# NFC_Shield.net
KiCad netlist of a schematic drawn in EAGLE
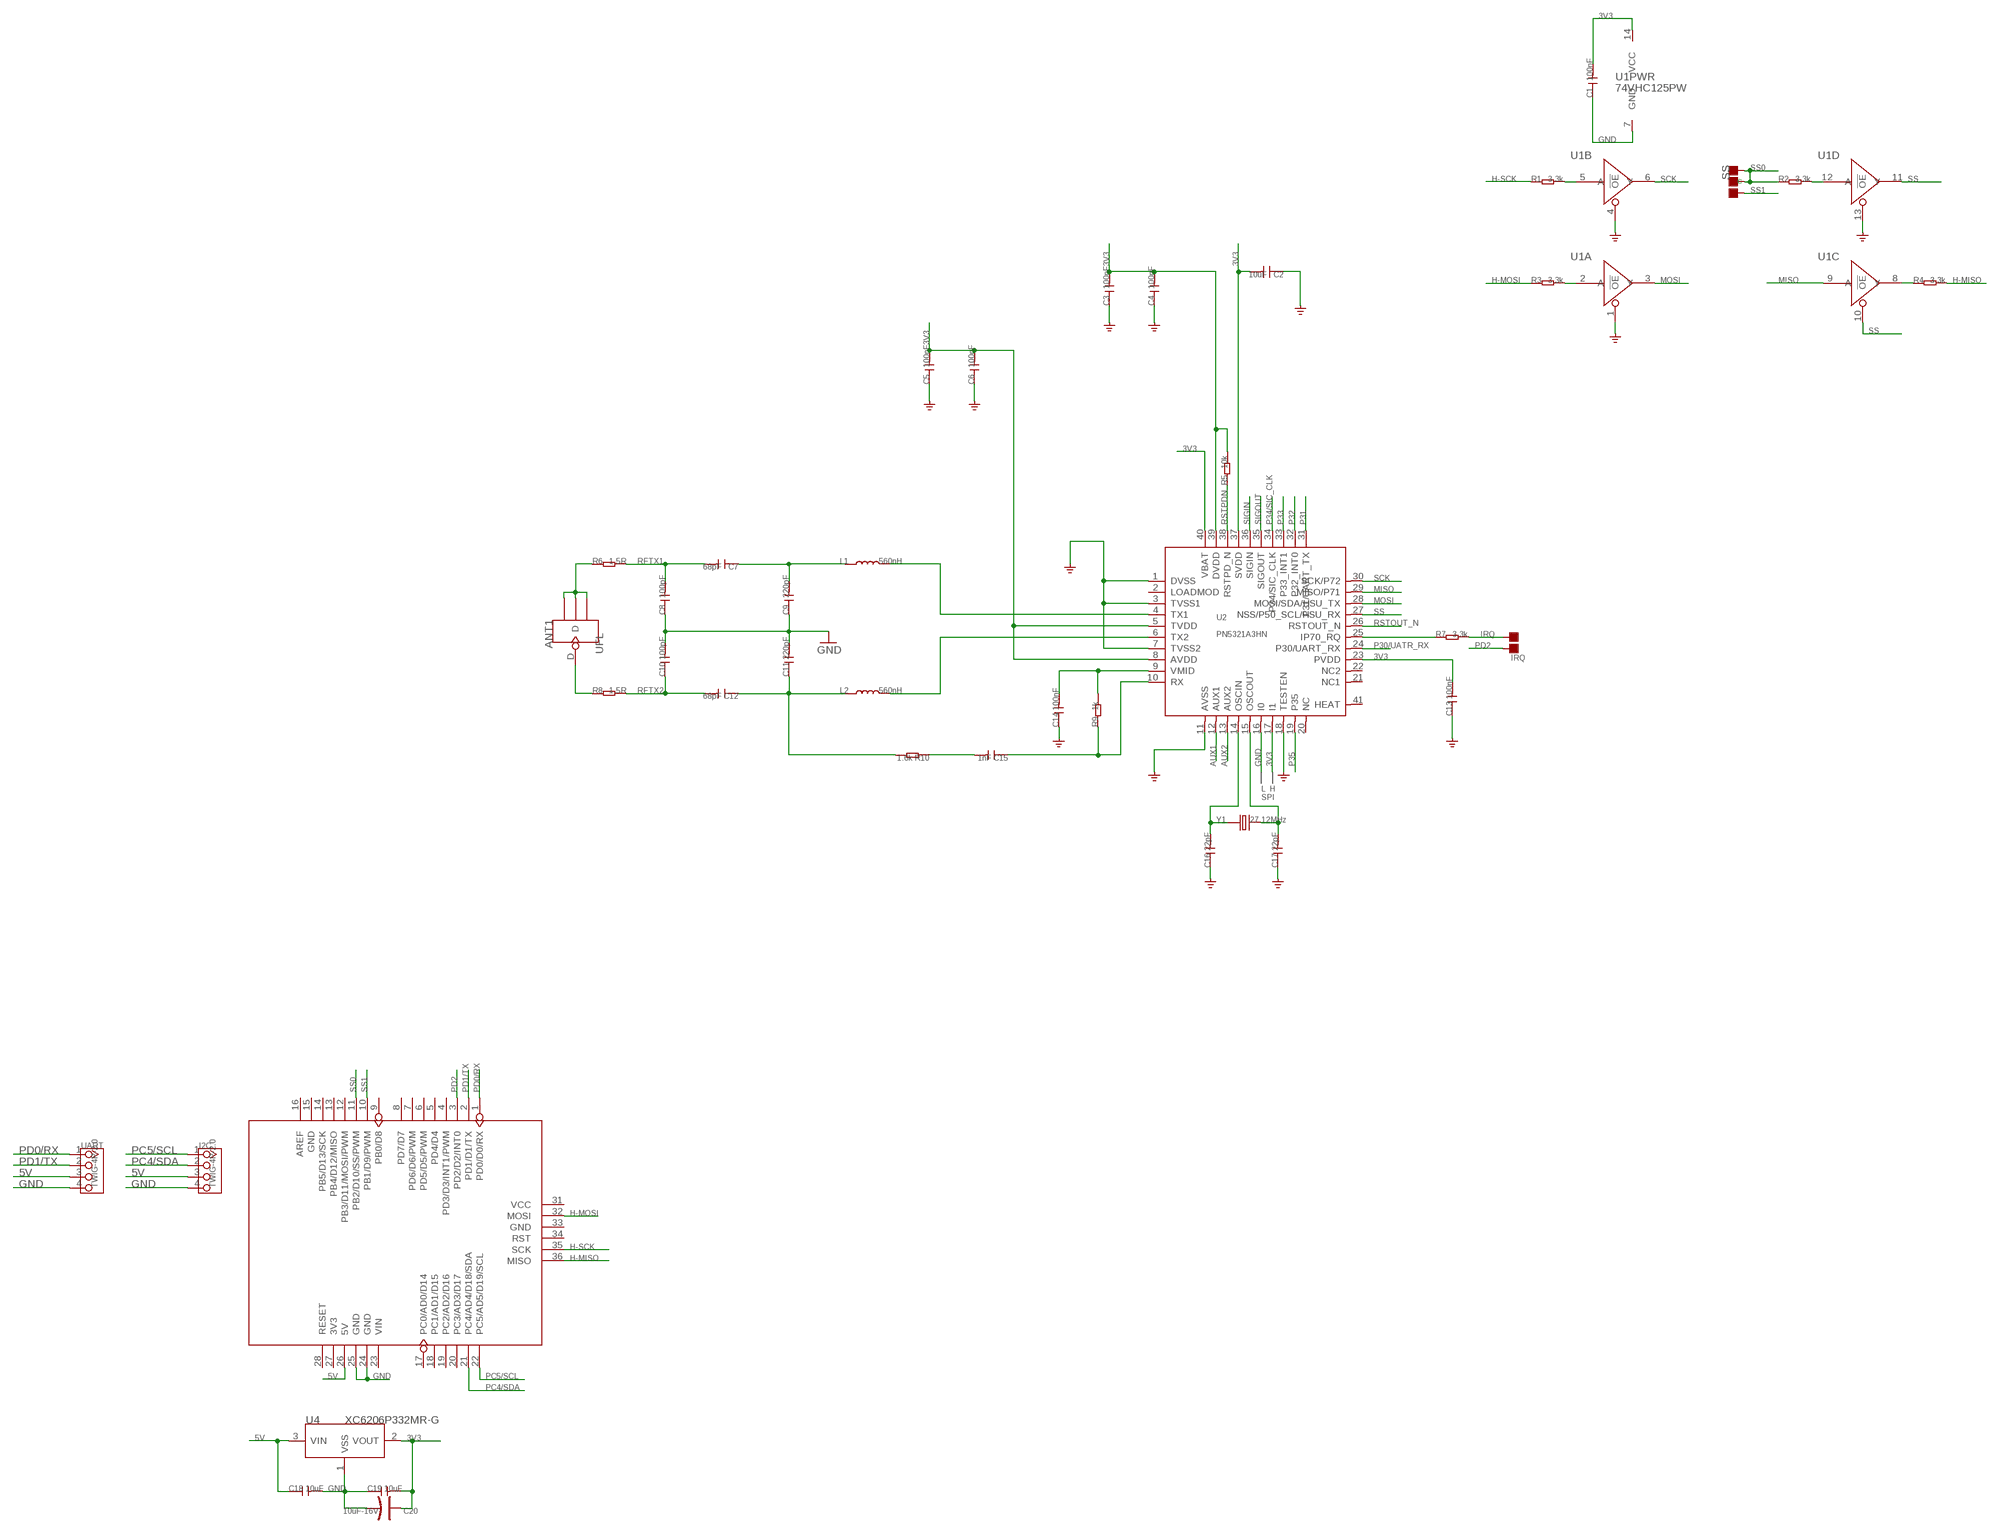
[diagram p0: schematic, sheet 1]

(export (version "E")
  (design (tool "Eeschema 10.0.6"))
  (components
    (comp (ref "ANT1")
      (value "UFL")
      (footprint "eagle-import:4P-U-FL")
      (libsource (lib "eagle-import") (part "ANTENNA-U-FL"))
    )
    (comp (ref "C1")
      (value "100nF")
      (footprint "eagle-import:C0603")
      (libsource (lib "eagle-import") (part "C-0603"))
    )
    (comp (ref "C2")
      (value "10uF")
      (footprint "eagle-import:0805")
      (libsource (lib "eagle-import") (part "Discreter_C-0805"))
    )
    (comp (ref "C3")
      (value "100nF")
      (footprint "eagle-import:C0603")
      (libsource (lib "eagle-import") (part "C-0603"))
    )
    (comp (ref "C4")
      (value "100nF")
      (footprint "eagle-import:C0603")
      (libsource (lib "eagle-import") (part "C-0603"))
    )
    (comp (ref "C5")
      (value "100nF")
      (footprint "eagle-import:C0603")
      (libsource (lib "eagle-import") (part "C-0603"))
    )
    (comp (ref "C6")
      (value "100nF")
      (footprint "eagle-import:C0603")
      (libsource (lib "eagle-import") (part "C-0603"))
    )
    (comp (ref "C7")
      (value "68pF")
      (footprint "eagle-import:C0603")
      (libsource (lib "eagle-import") (part "C-0603"))
    )
    (comp (ref "C8")
      (value "100pF")
      (footprint "eagle-import:C0603")
      (libsource (lib "eagle-import") (part "C-0603"))
    )
    (comp (ref "C9")
      (value "220pF")
      (footprint "eagle-import:C0603")
      (libsource (lib "eagle-import") (part "C-0603"))
    )
    (comp (ref "C10")
      (value "100pF")
      (footprint "eagle-import:C0603")
      (libsource (lib "eagle-import") (part "C-0603"))
    )
    (comp (ref "C11")
      (value "220pF")
      (footprint "eagle-import:C0603")
      (libsource (lib "eagle-import") (part "C-0603"))
    )
    (comp (ref "C12")
      (value "68pF")
      (footprint "eagle-import:C0603")
      (libsource (lib "eagle-import") (part "C-0603"))
    )
    (comp (ref "C13")
      (value "100nF")
      (footprint "eagle-import:C0603")
      (libsource (lib "eagle-import") (part "C-0603"))
    )
    (comp (ref "C14")
      (value "100nF")
      (footprint "eagle-import:C0603")
      (libsource (lib "eagle-import") (part "C-0603"))
    )
    (comp (ref "C15")
      (value "1nF")
      (footprint "eagle-import:C0603")
      (libsource (lib "eagle-import") (part "C-0603"))
    )
    (comp (ref "C16")
      (value "22pF")
      (footprint "eagle-import:C0603")
      (libsource (lib "eagle-import") (part "C-0603"))
    )
    (comp (ref "C17")
      (value "22pF")
      (footprint "eagle-import:C0603")
      (libsource (lib "eagle-import") (part "C-0603"))
    )
    (comp (ref "C18")
      (value "10uF")
      (footprint "eagle-import:C0805")
      (libsource (lib "eagle-import") (part "C-0805"))
    )
    (comp (ref "C19")
      (value "10uF")
      (footprint "eagle-import:C0805")
      (libsource (lib "eagle-import") (part "C-0805"))
    )
    (comp (ref "C20")
      (value "10uF-16V")
      (footprint "eagle-import:AVX-A")
      (libsource (lib "eagle-import") (part "CAP-AVX-A"))
    )
    (comp (ref "I2C")
      (value "TWIG-4P-2.0")
      (footprint "eagle-import:4P-2.0")
      (libsource (lib "eagle-import") (part "TWIG-4P-2.0-2.0"))
    )
    (comp (ref "IRQ")
      (value "DNP")
      (footprint "eagle-import:2P-SMD-1.78X1.27")
      (libsource (lib "eagle-import") (part "PAD-JUMPER-2P"))
    )
    (comp (ref "L1")
      (value "560nH")
      (footprint "eagle-import:L0805")
      (libsource (lib "eagle-import") (part "L'0805'"))
    )
    (comp (ref "L2")
      (value "560nH")
      (footprint "eagle-import:L0805")
      (libsource (lib "eagle-import") (part "L'0805'"))
    )
    (comp (ref "R1")
      (value "3.3k")
      (footprint "eagle-import:R0603")
      (libsource (lib "eagle-import") (part "R-0603"))
    )
    (comp (ref "R2")
      (value "3.3k")
      (footprint "eagle-import:R0603")
      (libsource (lib "eagle-import") (part "R-0603"))
    )
    (comp (ref "R3")
      (value "3.3k")
      (footprint "eagle-import:R0603")
      (libsource (lib "eagle-import") (part "R-0603"))
    )
    (comp (ref "R4")
      (value "3.3k")
      (footprint "eagle-import:R0603")
      (libsource (lib "eagle-import") (part "R-0603"))
    )
    (comp (ref "R5")
      (value "10k")
      (footprint "eagle-import:R0603")
      (libsource (lib "eagle-import") (part "R-0603"))
    )
    (comp (ref "R6")
      (value "1.5R")
      (footprint "eagle-import:R0603")
      (libsource (lib "eagle-import") (part "R-0603"))
    )
    (comp (ref "R7")
      (value "3.3k")
      (footprint "eagle-import:R0603")
      (libsource (lib "eagle-import") (part "R-0603"))
    )
    (comp (ref "R8")
      (value "1.5R")
      (footprint "eagle-import:R0603")
      (libsource (lib "eagle-import") (part "R-0603"))
    )
    (comp (ref "R9")
      (value "1k")
      (footprint "eagle-import:R0603")
      (libsource (lib "eagle-import") (part "R-0603"))
    )
    (comp (ref "R10")
      (value "1.6k")
      (footprint "eagle-import:R0603")
      (libsource (lib "eagle-import") (part "R-0603"))
    )
    (comp (ref "SS")
      (value "DNP")
      (footprint "eagle-import:3P-SMD-4.1X1.5")
      (libsource (lib "eagle-import") (part "PAD-JUMPER-3P-4040"))
    )
    (comp (ref "U1")
      (value "74VHC125PW")
      (footprint "eagle-import:TSSOP14")
      (libsource (lib "eagle-import") (part "74V125PWHC"))
    )
    (comp (ref "U2")
      (value "PN5321A3HN")
      (footprint "eagle-import:HVQFN40")
      (libsource (lib "eagle-import") (part "PN532-HVQFN40"))
    )
    (comp (ref "U3")
      (value "ARDUINO'W/-SILK")
      (footprint "eagle-import:ARDUINO")
      (libsource (lib "eagle-import") (part "ARDUINO'W/-SILK"))
    )
    (comp (ref "U4")
      (value "XC6206P332MR-G")
      (footprint "eagle-import:SOT23")
      (libsource (lib "eagle-import") (part "XC6206MR"))
    )
    (comp (ref "UART")
      (value "TWIG-4P-2.0")
      (footprint "eagle-import:4P-2.0")
      (libsource (lib "eagle-import") (part "TWIG-4P-2.0-2.0"))
    )
    (comp (ref "Y1")
      (value "27.12MHz")
      (footprint "eagle-import:HC49_S")
      (libsource (lib "eagle-import") (part "CRYSTAL'HC49S'"))
    )
  )
  (nets
    (net (code "1") (name "/3V3") (class "Default")
      (node (ref "C1") (pin "2") (pinfunction "2_2") (pintype "passive"))
      (node (ref "C13") (pin "2") (pinfunction "2_2") (pintype "passive"))
      (node (ref "C19") (pin "2") (pinfunction "2_2") (pintype "passive"))
      (node (ref "C2") (pin "2") (pinfunction "2_2") (pintype "passive"))
      (node (ref "C20") (pin "+") (pinfunction "+_+") (pintype "passive"))
      (node (ref "C3") (pin "2") (pinfunction "2_2") (pintype "passive"))
      (node (ref "C4") (pin "2") (pinfunction "2_2") (pintype "passive"))
      (node (ref "C5") (pin "2") (pinfunction "2_2") (pintype "passive"))
      (node (ref "C6") (pin "2") (pinfunction "2_2") (pintype "passive"))
      (node (ref "R5") (pin "2") (pinfunction "2_2") (pintype "passive"))
      (node (ref "U1") (pin "14") (pinfunction "VCC_14") (pintype "power_in"))
      (node (ref "U2") (pin "17") (pinfunction "I1_17") (pintype "input"))
      (node (ref "U2") (pin "23") (pinfunction "PVDD_23") (pintype "power_in"))
      (node (ref "U2") (pin "37") (pinfunction "SVDD_37") (pintype "power_in"))
      (node (ref "U2") (pin "39") (pinfunction "DVDD_39") (pintype "power_in"))
      (node (ref "U2") (pin "40") (pinfunction "VBAT_40") (pintype "power_in"))
      (node (ref "U2") (pin "5") (pinfunction "TVDD_5") (pintype "power_in"))
      (node (ref "U2") (pin "8") (pinfunction "AVDD_8") (pintype "power_in"))
      (node (ref "U4") (pin "2") (pinfunction "VOUT_2") (pintype "output"))
    )
    (net (code "2") (name "/5V") (class "Default")
      (node (ref "C18") (pin "1") (pinfunction "1_1") (pintype "passive"))
      (node (ref "I2C") (pin "3") (pinfunction "3_3") (pintype "bidirectional"))
      (node (ref "U3") (pin "26") (pinfunction "5V_26") (pintype "bidirectional"))
      (node (ref "U4") (pin "3") (pinfunction "VIN_3") (pintype "input"))
      (node (ref "UART") (pin "3") (pinfunction "3_3") (pintype "bidirectional"))
    )
    (net (code "3") (name "/AUX1") (class "Default")
      (node (ref "U2") (pin "12") (pinfunction "AUX1_12") (pintype "output"))
    )
    (net (code "4") (name "/AUX2") (class "Default")
      (node (ref "U2") (pin "13") (pinfunction "AUX2_13") (pintype "output"))
    )
    (net (code "5") (name "/H-MISO") (class "Default")
      (node (ref "R4") (pin "2") (pinfunction "2_2") (pintype "passive"))
      (node (ref "U3") (pin "36") (pinfunction "MISO_36") (pintype "bidirectional"))
    )
    (net (code "6") (name "/H-MOSI") (class "Default")
      (node (ref "R3") (pin "1") (pinfunction "1_1") (pintype "passive"))
      (node (ref "U3") (pin "32") (pinfunction "MOSI_32") (pintype "bidirectional"))
    )
    (net (code "7") (name "/H-SCK") (class "Default")
      (node (ref "R1") (pin "1") (pinfunction "1_1") (pintype "passive"))
      (node (ref "U3") (pin "35") (pinfunction "SCK_35") (pintype "bidirectional"))
    )
    (net (code "8") (name "/IRQ") (class "Default")
      (node (ref "IRQ") (pin "1") (pinfunction "1_1") (pintype "bidirectional"))
      (node (ref "R7") (pin "2") (pinfunction "2_2") (pintype "passive"))
    )
    (net (code "9") (name "/MISO") (class "Default")
      (node (ref "U1") (pin "9") (pinfunction "A_9") (pintype "bidirectional"))
      (node (ref "U2") (pin "29") (pinfunction "MISO/P71_29") (pintype "bidirectional"))
    )
    (net (code "10") (name "/MOSI") (class "Default")
      (node (ref "U1") (pin "3") (pinfunction "Y_3") (pintype "bidirectional"))
      (node (ref "U2") (pin "28") (pinfunction "MOSI/SDA/HSU_TX_28") (pintype "bidirectional"))
    )
    (net (code "11") (name "/P30{slash}UATR_RX") (class "Default")
      (node (ref "U2") (pin "24") (pinfunction "P30/UART_RX_24") (pintype "bidirectional"))
    )
    (net (code "12") (name "/P31") (class "Default")
      (node (ref "U2") (pin "31") (pinfunction "P31/UART_TX_31") (pintype "bidirectional"))
    )
    (net (code "13") (name "/P32") (class "Default")
      (node (ref "U2") (pin "32") (pinfunction "P32_INT0_32") (pintype "bidirectional"))
    )
    (net (code "14") (name "/P33") (class "Default")
      (node (ref "U2") (pin "33") (pinfunction "P33_INT1_33") (pintype "bidirectional"))
    )
    (net (code "15") (name "/P34{slash}SIC_CLK") (class "Default")
      (node (ref "U2") (pin "34") (pinfunction "P34/SIC_CLK_34") (pintype "bidirectional"))
    )
    (net (code "16") (name "/P35") (class "Default")
      (node (ref "U2") (pin "19") (pinfunction "P35_19") (pintype "bidirectional"))
    )
    (net (code "17") (name "/PC4{slash}SDA") (class "Default")
      (node (ref "I2C") (pin "2") (pinfunction "2_2") (pintype "bidirectional"))
      (node (ref "U3") (pin "21") (pinfunction "PC4/AD4/D18/SDA_21") (pintype "bidirectional"))
    )
    (net (code "18") (name "/PC5{slash}SCL") (class "Default")
      (node (ref "I2C") (pin "1") (pinfunction "1_1") (pintype "bidirectional"))
      (node (ref "U3") (pin "22") (pinfunction "PC5/AD5/D19/SCL_22") (pintype "bidirectional"))
    )
    (net (code "19") (name "/PD0{slash}RX") (class "Default")
      (node (ref "U3") (pin "1") (pinfunction "PD0/D0/RX_1") (pintype "bidirectional"))
      (node (ref "UART") (pin "1") (pinfunction "1_1") (pintype "bidirectional"))
    )
    (net (code "20") (name "/PD1{slash}TX") (class "Default")
      (node (ref "U3") (pin "2") (pinfunction "PD1/D1/TX_2") (pintype "bidirectional"))
      (node (ref "UART") (pin "2") (pinfunction "2_2") (pintype "bidirectional"))
    )
    (net (code "21") (name "/PD2") (class "Default")
      (node (ref "IRQ") (pin "2") (pinfunction "2_2") (pintype "bidirectional"))
      (node (ref "U3") (pin "3") (pinfunction "PD2/D2/INT0_3") (pintype "bidirectional"))
    )
    (net (code "22") (name "/RFTX1") (class "Default")
      (node (ref "C7") (pin "2") (pinfunction "2_2") (pintype "passive"))
      (node (ref "C8") (pin "2") (pinfunction "2_2") (pintype "passive"))
      (node (ref "R6") (pin "2") (pinfunction "2_2") (pintype "passive"))
    )
    (net (code "23") (name "/RFTX2") (class "Default")
      (node (ref "C10") (pin "1") (pinfunction "1_1") (pintype "passive"))
      (node (ref "C12") (pin "2") (pinfunction "2_2") (pintype "passive"))
      (node (ref "R8") (pin "2") (pinfunction "2_2") (pintype "passive"))
    )
    (net (code "24") (name "/RSTOUT_N") (class "Default")
      (node (ref "U2") (pin "26") (pinfunction "RSTOUT_N_26") (pintype "bidirectional"))
    )
    (net (code "25") (name "/RSTPDN") (class "Default")
      (node (ref "R5") (pin "1") (pinfunction "1_1") (pintype "passive"))
      (node (ref "U2") (pin "38") (pinfunction "RSTPD_N_38") (pintype "input"))
    )
    (net (code "26") (name "/SCK") (class "Default")
      (node (ref "U1") (pin "6") (pinfunction "Y_6") (pintype "bidirectional"))
      (node (ref "U2") (pin "30") (pinfunction "SCK/P72_30") (pintype "bidirectional"))
    )
    (net (code "27") (name "/SIGIN") (class "Default")
      (node (ref "U2") (pin "36") (pinfunction "SIGIN_36") (pintype "input"))
    )
    (net (code "28") (name "/SIGOUT") (class "Default")
      (node (ref "U2") (pin "35") (pinfunction "SIGOUT_35") (pintype "output"))
    )
    (net (code "29") (name "/SS") (class "Default")
      (node (ref "U1") (pin "10") (pinfunction "~{OE}_10") (pintype "bidirectional"))
      (node (ref "U1") (pin "11") (pinfunction "Y_11") (pintype "bidirectional"))
      (node (ref "U2") (pin "27") (pinfunction "NSS/P50_SCL/HSU_RX_27") (pintype "bidirectional"))
    )
    (net (code "30") (name "/SS0") (class "Default")
      (node (ref "R2") (pin "1") (pinfunction "1_1") (pintype "passive"))
      (node (ref "SS") (pin "11") (pinfunction "R_11") (pintype "bidirectional"))
      (node (ref "SS") (pin "MM") (pinfunction "C_MM") (pintype "bidirectional"))
      (node (ref "U3") (pin "11") (pinfunction "PB2/D10/SS/PWM_11") (pintype "bidirectional"))
    )
    (net (code "31") (name "/SS1") (class "Default")
      (node (ref "SS") (pin "00") (pinfunction "L_00") (pintype "bidirectional"))
      (node (ref "U3") (pin "10") (pinfunction "PB1/D9/PWM_10") (pintype "bidirectional"))
    )
    (net (code "32") (name "GND") (class "Default")
      (node (ref "C1") (pin "1") (pinfunction "1_1") (pintype "passive"))
      (node (ref "C10") (pin "2") (pinfunction "2_2") (pintype "passive"))
      (node (ref "C11") (pin "2") (pinfunction "2_2") (pintype "passive"))
      (node (ref "C13") (pin "1") (pinfunction "1_1") (pintype "passive"))
      (node (ref "C14") (pin "1") (pinfunction "1_1") (pintype "passive"))
      (node (ref "C16") (pin "1") (pinfunction "1_1") (pintype "passive"))
      (node (ref "C17") (pin "1") (pinfunction "1_1") (pintype "passive"))
      (node (ref "C18") (pin "2") (pinfunction "2_2") (pintype "passive"))
      (node (ref "C19") (pin "1") (pinfunction "1_1") (pintype "passive"))
      (node (ref "C2") (pin "1") (pinfunction "1_1") (pintype "passive"))
      (node (ref "C20") (pin "-") (pinfunction "-_-") (pintype "passive"))
      (node (ref "C3") (pin "1") (pinfunction "1_1") (pintype "passive"))
      (node (ref "C4") (pin "1") (pinfunction "1_1") (pintype "passive"))
      (node (ref "C5") (pin "1") (pinfunction "1_1") (pintype "passive"))
      (node (ref "C6") (pin "1") (pinfunction "1_1") (pintype "passive"))
      (node (ref "C8") (pin "1") (pinfunction "1_1") (pintype "passive"))
      (node (ref "C9") (pin "1") (pinfunction "1_1") (pintype "passive"))
      (node (ref "I2C") (pin "4") (pinfunction "4_4") (pintype "bidirectional"))
      (node (ref "U1") (pin "1") (pinfunction "~{OE}_1") (pintype "bidirectional"))
      (node (ref "U1") (pin "13") (pinfunction "~{OE}_13") (pintype "bidirectional"))
      (node (ref "U1") (pin "4") (pinfunction "~{OE}_4") (pintype "bidirectional"))
      (node (ref "U1") (pin "7") (pinfunction "GND_7") (pintype "power_in"))
      (node (ref "U2") (pin "1") (pinfunction "DVSS_1") (pintype "power_in"))
      (node (ref "U2") (pin "11") (pinfunction "AVSS_11") (pintype "power_in"))
      (node (ref "U2") (pin "16") (pinfunction "I0_16") (pintype "input"))
      (node (ref "U2") (pin "18") (pinfunction "TESTEN_18") (pintype "input"))
      (node (ref "U2") (pin "3") (pinfunction "TVSS1_3") (pintype "power_in"))
      (node (ref "U2") (pin "7") (pinfunction "TVSS2_7") (pintype "power_in"))
      (node (ref "U3") (pin "24") (pinfunction "GND_24") (pintype "bidirectional"))
      (node (ref "U3") (pin "25") (pinfunction "GND_25") (pintype "bidirectional"))
      (node (ref "U4") (pin "1") (pinfunction "VSS_1") (pintype "power_in"))
      (node (ref "UART") (pin "4") (pinfunction "4_4") (pintype "bidirectional"))
    )
    (net (code "33") (name "Net-(ANT1-PadD)") (class "Default")
      (node (ref "ANT1") (pin "D") (pinfunction "D_D") (pintype "bidirectional"))
      (node (ref "R8") (pin "1") (pinfunction "1_1") (pintype "passive"))
    )
    (net (code "34") (name "Net-(ANT1-PadGND1)") (class "Default")
      (node (ref "ANT1") (pin "GND1") (pinfunction "GND1_GND1") (pintype "bidirectional"))
      (node (ref "ANT1") (pin "GND2") (pinfunction "GND2_GND2") (pintype "bidirectional"))
      (node (ref "ANT1") (pin "GND3") (pinfunction "GND3_GND3") (pintype "bidirectional"))
      (node (ref "R6") (pin "1") (pinfunction "1_1") (pintype "passive"))
    )
    (net (code "35") (name "Net-(C7-Pad1)") (class "Default")
      (node (ref "C7") (pin "1") (pinfunction "1_1") (pintype "passive"))
      (node (ref "C9") (pin "2") (pinfunction "2_2") (pintype "passive"))
      (node (ref "L1") (pin "1") (pinfunction "1_1") (pintype "passive"))
    )
    (net (code "36") (name "Net-(C11-Pad1)") (class "Default")
      (node (ref "C11") (pin "1") (pinfunction "1_1") (pintype "passive"))
      (node (ref "C12") (pin "1") (pinfunction "1_1") (pintype "passive"))
      (node (ref "L2") (pin "1") (pinfunction "1_1") (pintype "passive"))
      (node (ref "R10") (pin "2") (pinfunction "2_2") (pintype "passive"))
    )
    (net (code "37") (name "Net-(C15-Pad2)") (class "Default")
      (node (ref "C15") (pin "2") (pinfunction "2_2") (pintype "passive"))
      (node (ref "R10") (pin "1") (pinfunction "1_1") (pintype "passive"))
    )
    (net (code "38") (name "Net-(U1A-A)") (class "Default")
      (node (ref "R3") (pin "2") (pinfunction "2_2") (pintype "passive"))
      (node (ref "U1") (pin "2") (pinfunction "A_2") (pintype "bidirectional"))
    )
    (net (code "39") (name "Net-(U1B-A)") (class "Default")
      (node (ref "R1") (pin "2") (pinfunction "2_2") (pintype "passive"))
      (node (ref "U1") (pin "5") (pinfunction "A_5") (pintype "bidirectional"))
    )
    (net (code "40") (name "Net-(U1C-Y)") (class "Default")
      (node (ref "R4") (pin "1") (pinfunction "1_1") (pintype "passive"))
      (node (ref "U1") (pin "8") (pinfunction "Y_8") (pintype "bidirectional"))
    )
    (net (code "41") (name "Net-(U1D-A)") (class "Default")
      (node (ref "R2") (pin "2") (pinfunction "2_2") (pintype "passive"))
      (node (ref "U1") (pin "12") (pinfunction "A_12") (pintype "bidirectional"))
    )
    (net (code "42") (name "Net-(U2-IP70_RQ)") (class "Default")
      (node (ref "R7") (pin "1") (pinfunction "1_1") (pintype "passive"))
      (node (ref "U2") (pin "25") (pinfunction "IP70_RQ_25") (pintype "output"))
    )
    (net (code "43") (name "Net-(U2-OSCIN)") (class "Default")
      (node (ref "C16") (pin "2") (pinfunction "2_2") (pintype "passive"))
      (node (ref "U2") (pin "14") (pinfunction "OSCIN_14") (pintype "input"))
      (node (ref "Y1") (pin "1") (pinfunction "1_1") (pintype "passive"))
    )
    (net (code "44") (name "Net-(U2-OSCOUT)") (class "Default")
      (node (ref "C17") (pin "2") (pinfunction "2_2") (pintype "passive"))
      (node (ref "U2") (pin "15") (pinfunction "OSCOUT_15") (pintype "output"))
      (node (ref "Y1") (pin "2") (pinfunction "2_2") (pintype "passive"))
    )
    (net (code "45") (name "Net-(U2-RX)") (class "Default")
      (node (ref "C15") (pin "1") (pinfunction "1_1") (pintype "passive"))
      (node (ref "R9") (pin "1") (pinfunction "1_1") (pintype "passive"))
      (node (ref "U2") (pin "10") (pinfunction "RX_10") (pintype "input"))
    )
    (net (code "46") (name "Net-(U2-TX1)") (class "Default")
      (node (ref "L1") (pin "2") (pinfunction "2_2") (pintype "passive"))
      (node (ref "U2") (pin "4") (pinfunction "TX1_4") (pintype "output"))
    )
    (net (code "47") (name "Net-(U2-TX2)") (class "Default")
      (node (ref "L2") (pin "2") (pinfunction "2_2") (pintype "passive"))
      (node (ref "U2") (pin "6") (pinfunction "TX2_6") (pintype "output"))
    )
    (net (code "48") (name "Net-(U2-VMID)") (class "Default")
      (node (ref "C14") (pin "2") (pinfunction "2_2") (pintype "passive"))
      (node (ref "R9") (pin "2") (pinfunction "2_2") (pintype "passive"))
      (node (ref "U2") (pin "9") (pinfunction "VMID_9") (pintype "output"))
    )
    (net (code "49") (name "unconnected-(U2-HEAT-Pad41)") (class "Default")
      (node (ref "U2") (pin "41") (pinfunction "HEAT_41") (pintype "bidirectional"))
    )
    (net (code "50") (name "unconnected-(U2-LOADMOD-Pad2)") (class "Default")
      (node (ref "U2") (pin "2") (pinfunction "LOADMOD_2") (pintype "output"))
    )
    (net (code "51") (name "unconnected-(U2-NC-Pad20)") (class "Default")
      (node (ref "U2") (pin "20") (pinfunction "NC_20") (pintype "no_connect"))
    )
    (net (code "52") (name "unconnected-(U2-NC1-Pad21)") (class "Default")
      (node (ref "U2") (pin "21") (pinfunction "NC1_21") (pintype "no_connect"))
    )
    (net (code "53") (name "unconnected-(U2-NC2-Pad22)") (class "Default")
      (node (ref "U2") (pin "22") (pinfunction "NC2_22") (pintype "no_connect"))
    )
    (net (code "54") (name "unconnected-(U3-3V3-Pad27)") (class "Default")
      (node (ref "U3") (pin "27") (pinfunction "3V3_27") (pintype "bidirectional"))
    )
    (net (code "55") (name "unconnected-(U3-AREF-Pad16)") (class "Default")
      (node (ref "U3") (pin "16") (pinfunction "AREF_16") (pintype "bidirectional"))
    )
    (net (code "56") (name "unconnected-(U3-GND-Pad15)") (class "Default")
      (node (ref "U3") (pin "15") (pinfunction "GND_15") (pintype "bidirectional"))
    )
    (net (code "57") (name "unconnected-(U3-GND-Pad33)") (class "Default")
      (node (ref "U3") (pin "33") (pinfunction "GND_33") (pintype "bidirectional"))
    )
    (net (code "58") (name "unconnected-(U3-PB0{slash}D8-Pad9)") (class "Default")
      (node (ref "U3") (pin "9") (pinfunction "PB0/D8_9") (pintype "bidirectional"))
    )
    (net (code "59") (name "unconnected-(U3-PB3{slash}D11{slash}MOSI{slash}PWM-Pad12)") (class "Default")
      (node (ref "U3") (pin "12") (pinfunction "PB3/D11/MOSI/PWM_12") (pintype "bidirectional"))
    )
    (net (code "60") (name "unconnected-(U3-PB4{slash}D12{slash}MISO-Pad13)") (class "Default")
      (node (ref "U3") (pin "13") (pinfunction "PB4/D12/MISO_13") (pintype "bidirectional"))
    )
    (net (code "61") (name "unconnected-(U3-PB5{slash}D13{slash}SCK-Pad14)") (class "Default")
      (node (ref "U3") (pin "14") (pinfunction "PB5/D13/SCK_14") (pintype "bidirectional"))
    )
    (net (code "62") (name "unconnected-(U3-PC0{slash}AD0{slash}D14-Pad17)") (class "Default")
      (node (ref "U3") (pin "17") (pinfunction "PC0/AD0/D14_17") (pintype "bidirectional"))
    )
    (net (code "63") (name "unconnected-(U3-PC1{slash}AD1{slash}D15-Pad18)") (class "Default")
      (node (ref "U3") (pin "18") (pinfunction "PC1/AD1/D15_18") (pintype "bidirectional"))
    )
    (net (code "64") (name "unconnected-(U3-PC2{slash}AD2{slash}D16-Pad19)") (class "Default")
      (node (ref "U3") (pin "19") (pinfunction "PC2/AD2/D16_19") (pintype "bidirectional"))
    )
    (net (code "65") (name "unconnected-(U3-PC3{slash}AD3{slash}D17-Pad20)") (class "Default")
      (node (ref "U3") (pin "20") (pinfunction "PC3/AD3/D17_20") (pintype "bidirectional"))
    )
    (net (code "66") (name "unconnected-(U3-PD3{slash}D3{slash}INT1{slash}PWM-Pad4)") (class "Default")
      (node (ref "U3") (pin "4") (pinfunction "PD3/D3/INT1/PWM_4") (pintype "bidirectional"))
    )
    (net (code "67") (name "unconnected-(U3-PD4{slash}D4-Pad5)") (class "Default")
      (node (ref "U3") (pin "5") (pinfunction "PD4/D4_5") (pintype "bidirectional"))
    )
    (net (code "68") (name "unconnected-(U3-PD5{slash}D5{slash}PWM-Pad6)") (class "Default")
      (node (ref "U3") (pin "6") (pinfunction "PD5/D5/PWM_6") (pintype "bidirectional"))
    )
    (net (code "69") (name "unconnected-(U3-PD6{slash}D6{slash}PWM-Pad7)") (class "Default")
      (node (ref "U3") (pin "7") (pinfunction "PD6/D6/PWM_7") (pintype "bidirectional"))
    )
    (net (code "70") (name "unconnected-(U3-PD7{slash}D7-Pad8)") (class "Default")
      (node (ref "U3") (pin "8") (pinfunction "PD7/D7_8") (pintype "bidirectional"))
    )
    (net (code "71") (name "unconnected-(U3-RESET-Pad28)") (class "Default")
      (node (ref "U3") (pin "28") (pinfunction "RESET_28") (pintype "bidirectional"))
    )
    (net (code "72") (name "unconnected-(U3-RST-Pad34)") (class "Default")
      (node (ref "U3") (pin "34") (pinfunction "RST_34") (pintype "bidirectional"))
    )
    (net (code "73") (name "unconnected-(U3-VCC-Pad31)") (class "Default")
      (node (ref "U3") (pin "31") (pinfunction "VCC_31") (pintype "bidirectional"))
    )
    (net (code "74") (name "unconnected-(U3-VIN-Pad23)") (class "Default")
      (node (ref "U3") (pin "23") (pinfunction "VIN_23") (pintype "bidirectional"))
    )
  )
)
